# ledsbrd.net
KiCad netlist of a schematic drawn in EAGLE
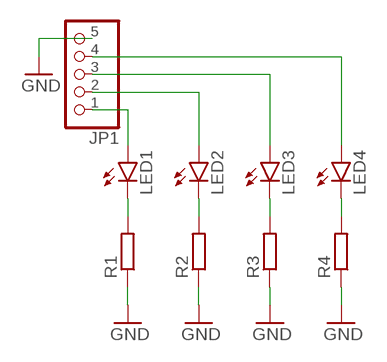
[diagram p0: schematic, sheet 1]

(export (version "E")
  (design (tool "Eeschema 10.0.6"))
  (components
    (comp (ref "JP1")
      (value "PINHD-1X5")
      (footprint "eagle-import:1X05")
      (libsource (lib "eagle-import") (part "PINHD-1X5"))
    )
    (comp (ref "LED1")
      (value "LED5MM")
      (footprint "eagle-import:LED5MM")
      (libsource (lib "eagle-import") (part "LED5MM"))
    )
    (comp (ref "LED2")
      (value "LED5MM")
      (footprint "eagle-import:LED5MM")
      (libsource (lib "eagle-import") (part "LED5MM"))
    )
    (comp (ref "LED3")
      (value "LED5MM")
      (footprint "eagle-import:LED5MM")
      (libsource (lib "eagle-import") (part "LED5MM"))
    )
    (comp (ref "LED4")
      (value "LED5MM")
      (footprint "eagle-import:LED5MM")
      (libsource (lib "eagle-import") (part "LED5MM"))
    )
    (comp (ref "R1")
      (value "R-EU_0204/5")
      (footprint "eagle-import:0204_5")
      (libsource (lib "eagle-import") (part "R-EU_0204/5"))
    )
    (comp (ref "R2")
      (value "R-EU_0204/5")
      (footprint "eagle-import:0204_5")
      (libsource (lib "eagle-import") (part "R-EU_0204/5"))
    )
    (comp (ref "R3")
      (value "R-EU_0204/5")
      (footprint "eagle-import:0204_5")
      (libsource (lib "eagle-import") (part "R-EU_0204/5"))
    )
    (comp (ref "R4")
      (value "R-EU_0204/5")
      (footprint "eagle-import:0204_5")
      (libsource (lib "eagle-import") (part "R-EU_0204/5"))
    )
  )
  (nets
    (net (code "1") (name "GND") (class "Default")
      (node (ref "JP1") (pin "5") (pinfunction "5_5") (pintype "passive"))
      (node (ref "R1") (pin "1") (pinfunction "1_1") (pintype "passive"))
      (node (ref "R2") (pin "1") (pinfunction "1_1") (pintype "passive"))
      (node (ref "R3") (pin "1") (pinfunction "1_1") (pintype "passive"))
      (node (ref "R4") (pin "1") (pinfunction "1_1") (pintype "passive"))
    )
    (net (code "2") (name "Net-(JP1-Pad1)") (class "Default")
      (node (ref "JP1") (pin "1") (pinfunction "1_1") (pintype "passive"))
      (node (ref "LED1") (pin "A") (pinfunction "A_A") (pintype "passive"))
    )
    (net (code "3") (name "Net-(JP1-Pad2)") (class "Default")
      (node (ref "JP1") (pin "2") (pinfunction "2_2") (pintype "passive"))
      (node (ref "LED2") (pin "A") (pinfunction "A_A") (pintype "passive"))
    )
    (net (code "4") (name "Net-(JP1-Pad3)") (class "Default")
      (node (ref "JP1") (pin "3") (pinfunction "3_3") (pintype "passive"))
      (node (ref "LED3") (pin "A") (pinfunction "A_A") (pintype "passive"))
    )
    (net (code "5") (name "Net-(JP1-Pad4)") (class "Default")
      (node (ref "JP1") (pin "4") (pinfunction "4_4") (pintype "passive"))
      (node (ref "LED4") (pin "A") (pinfunction "A_A") (pintype "passive"))
    )
    (net (code "6") (name "Net-(LED1-C)") (class "Default")
      (node (ref "LED1") (pin "K") (pinfunction "C_K") (pintype "passive"))
      (node (ref "R1") (pin "2") (pinfunction "2_2") (pintype "passive"))
    )
    (net (code "7") (name "Net-(LED2-C)") (class "Default")
      (node (ref "LED2") (pin "K") (pinfunction "C_K") (pintype "passive"))
      (node (ref "R2") (pin "2") (pinfunction "2_2") (pintype "passive"))
    )
    (net (code "8") (name "Net-(LED3-C)") (class "Default")
      (node (ref "LED3") (pin "K") (pinfunction "C_K") (pintype "passive"))
      (node (ref "R3") (pin "2") (pinfunction "2_2") (pintype "passive"))
    )
    (net (code "9") (name "Net-(LED4-C)") (class "Default")
      (node (ref "LED4") (pin "K") (pinfunction "C_K") (pintype "passive"))
      (node (ref "R4") (pin "2") (pinfunction "2_2") (pintype "passive"))
    )
  )
)
